# Grove_-_HCHO_Sensor.net
KiCad netlist of a schematic drawn in EAGLE
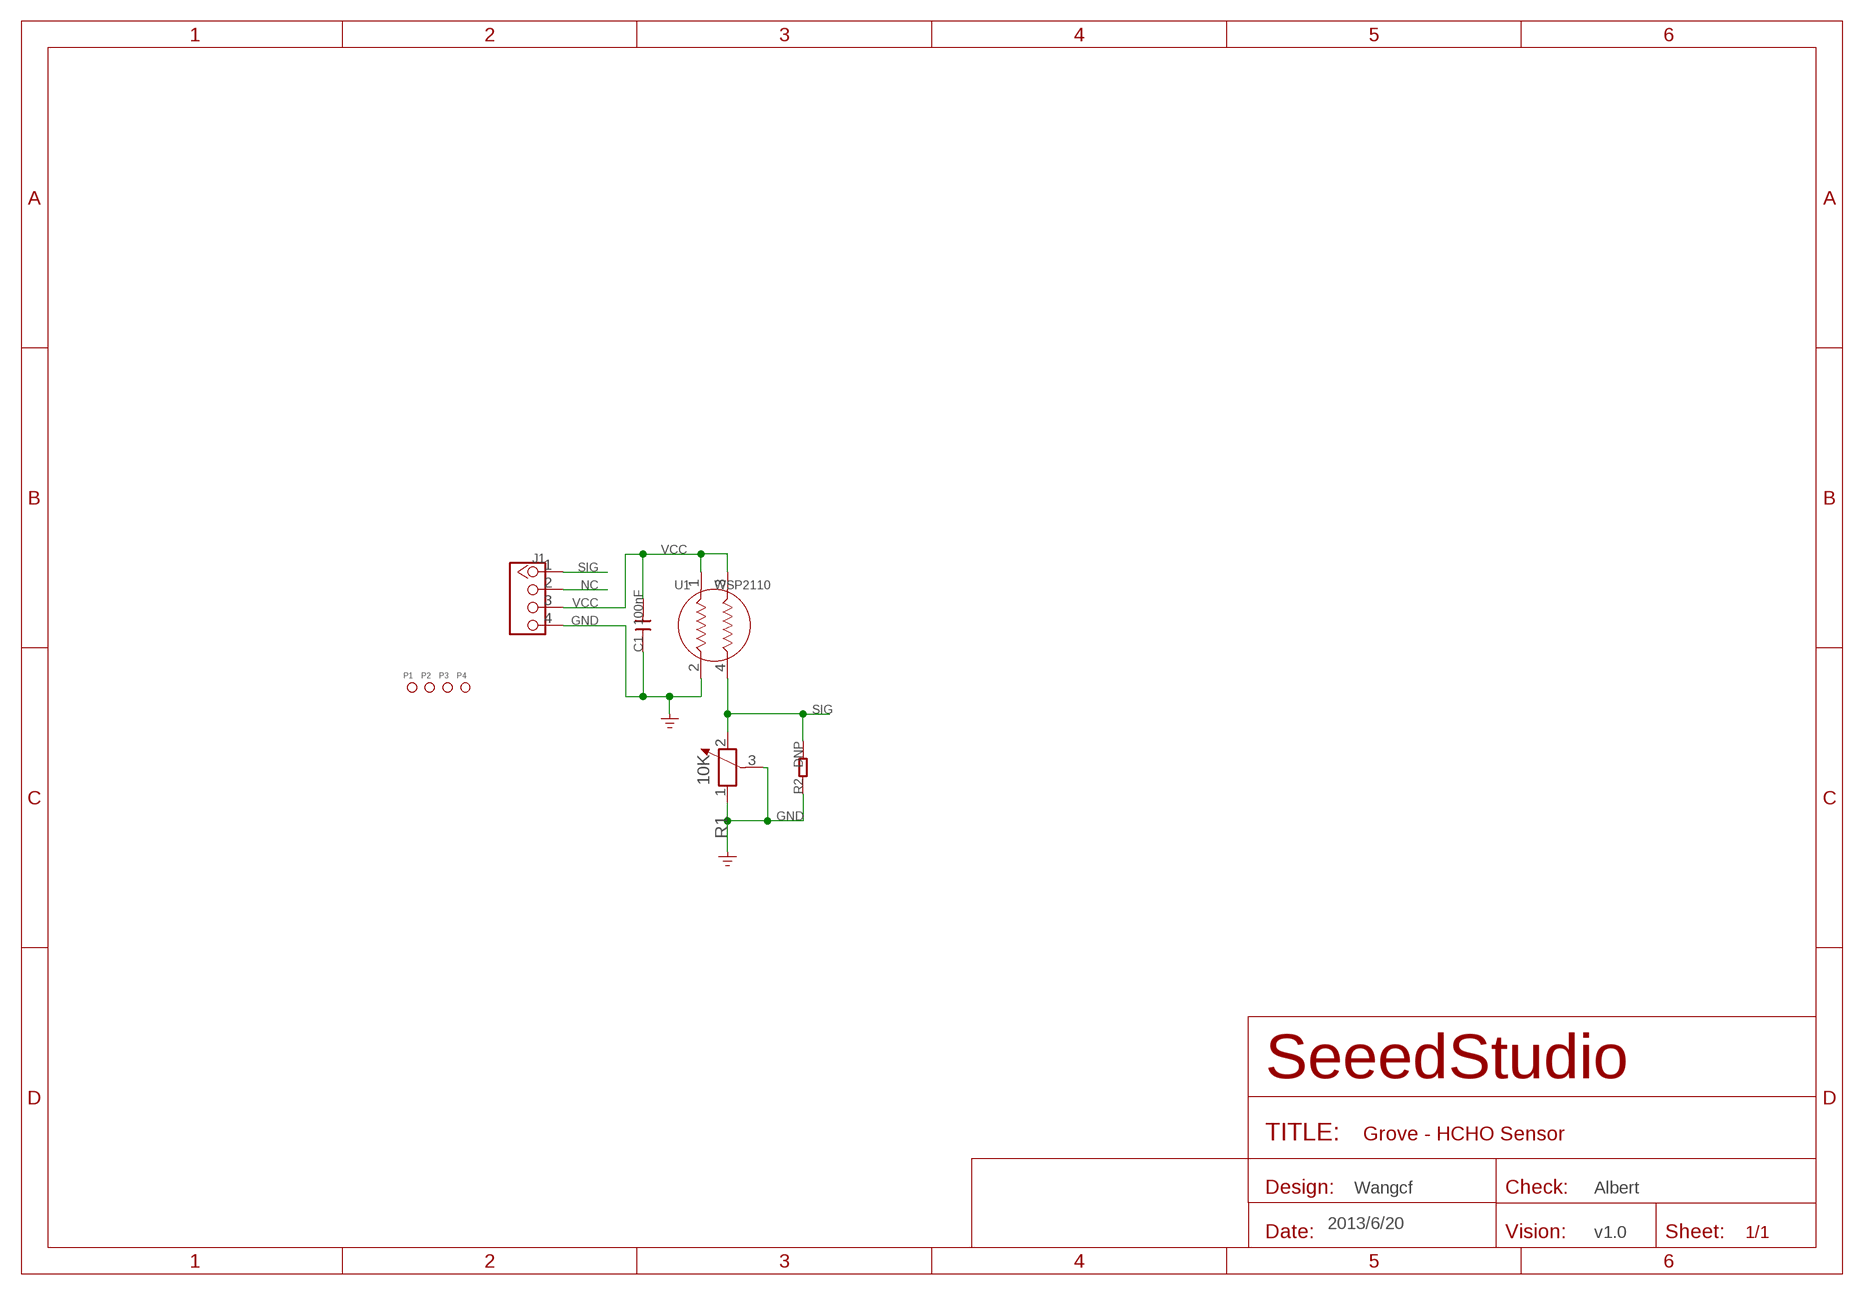
[diagram p0: schematic, sheet 1]

(export (version "E")
  (design (tool "Eeschema 10.0.6"))
  (components
    (comp (ref "C1")
      (value "100nF")
      (footprint "eagle-import:C0603")
      (libsource (lib "eagle-import") (part "C-0603"))
    )
    (comp (ref "J1")
      (value "TWIG-4P-2.0-2.0")
      (footprint "eagle-import:4P-2.0")
      (libsource (lib "eagle-import") (part "TWIG-4P-2.0-2.0"))
    )
    (comp (ref "P1")
      (value "PAD-MARK")
      (footprint "eagle-import:ROUND-MARK-1.0")
      (fields (field (name "PARTNO") "DNP"))
      (libsource (lib "eagle-import") (part "PAD-MARK"))
    )
    (comp (ref "P2")
      (value "PAD-MARK")
      (footprint "eagle-import:ROUND-MARK-1.0")
      (fields (field (name "PARTNO") "DNP"))
      (libsource (lib "eagle-import") (part "PAD-MARK"))
    )
    (comp (ref "P3")
      (value "PAD-MARK")
      (footprint "eagle-import:ROUND-MARK-1.0")
      (fields (field (name "PARTNO") "DNP"))
      (libsource (lib "eagle-import") (part "PAD-MARK"))
    )
    (comp (ref "P4")
      (value "PAD-MARK")
      (footprint "eagle-import:ROUND-MARK-1.0")
      (fields (field (name "PARTNO") "DNP"))
      (libsource (lib "eagle-import") (part "PAD-MARK"))
    )
    (comp (ref "R1")
      (value "10K")
      (footprint "eagle-import:3P-SQUA-7X6.8")
      (libsource (lib "eagle-import") (part "R-POTENTIOMETER'3362'"))
    )
    (comp (ref "R2")
      (value "DNP")
      (footprint "eagle-import:R0603")
      (libsource (lib "eagle-import") (part "R-0603"))
    )
    (comp (ref "U1")
      (value "WSP2110")
      (footprint "eagle-import:4P-D9.4-7.5H")
      (libsource (lib "eagle-import") (part "WSP2110"))
    )
  )
  (nets
    (net (code "1") (name "/NC") (class "Default")
      (node (ref "J1") (pin "2") (pinfunction "2_2") (pintype "bidirectional"))
    )
    (net (code "2") (name "/SIG") (class "Default")
      (node (ref "J1") (pin "1") (pinfunction "1_1") (pintype "bidirectional"))
      (node (ref "R1") (pin "2") (pinfunction "2_2") (pintype "passive"))
      (node (ref "R2") (pin "2") (pinfunction "2_2") (pintype "passive"))
      (node (ref "U1") (pin "4") (pinfunction "4_4") (pintype "bidirectional"))
    )
    (net (code "3") (name "/VCC") (class "Default")
      (node (ref "C1") (pin "2") (pinfunction "2_2") (pintype "passive"))
      (node (ref "J1") (pin "3") (pinfunction "3_3") (pintype "bidirectional"))
      (node (ref "U1") (pin "1") (pinfunction "1_1") (pintype "bidirectional"))
      (node (ref "U1") (pin "3") (pinfunction "3_3") (pintype "bidirectional"))
    )
    (net (code "4") (name "GND_POWER") (class "Default")
      (node (ref "C1") (pin "1") (pinfunction "1_1") (pintype "passive"))
      (node (ref "J1") (pin "4") (pinfunction "4_4") (pintype "bidirectional"))
      (node (ref "R1") (pin "1") (pinfunction "1_1") (pintype "passive"))
      (node (ref "R1") (pin "3") (pinfunction "3_3") (pintype "passive"))
      (node (ref "R2") (pin "1") (pinfunction "1_1") (pintype "passive"))
      (node (ref "U1") (pin "2") (pinfunction "2_2") (pintype "bidirectional"))
    )
  )
)
